# CC2530.net
KiCad netlist of a schematic drawn in Altium Designer
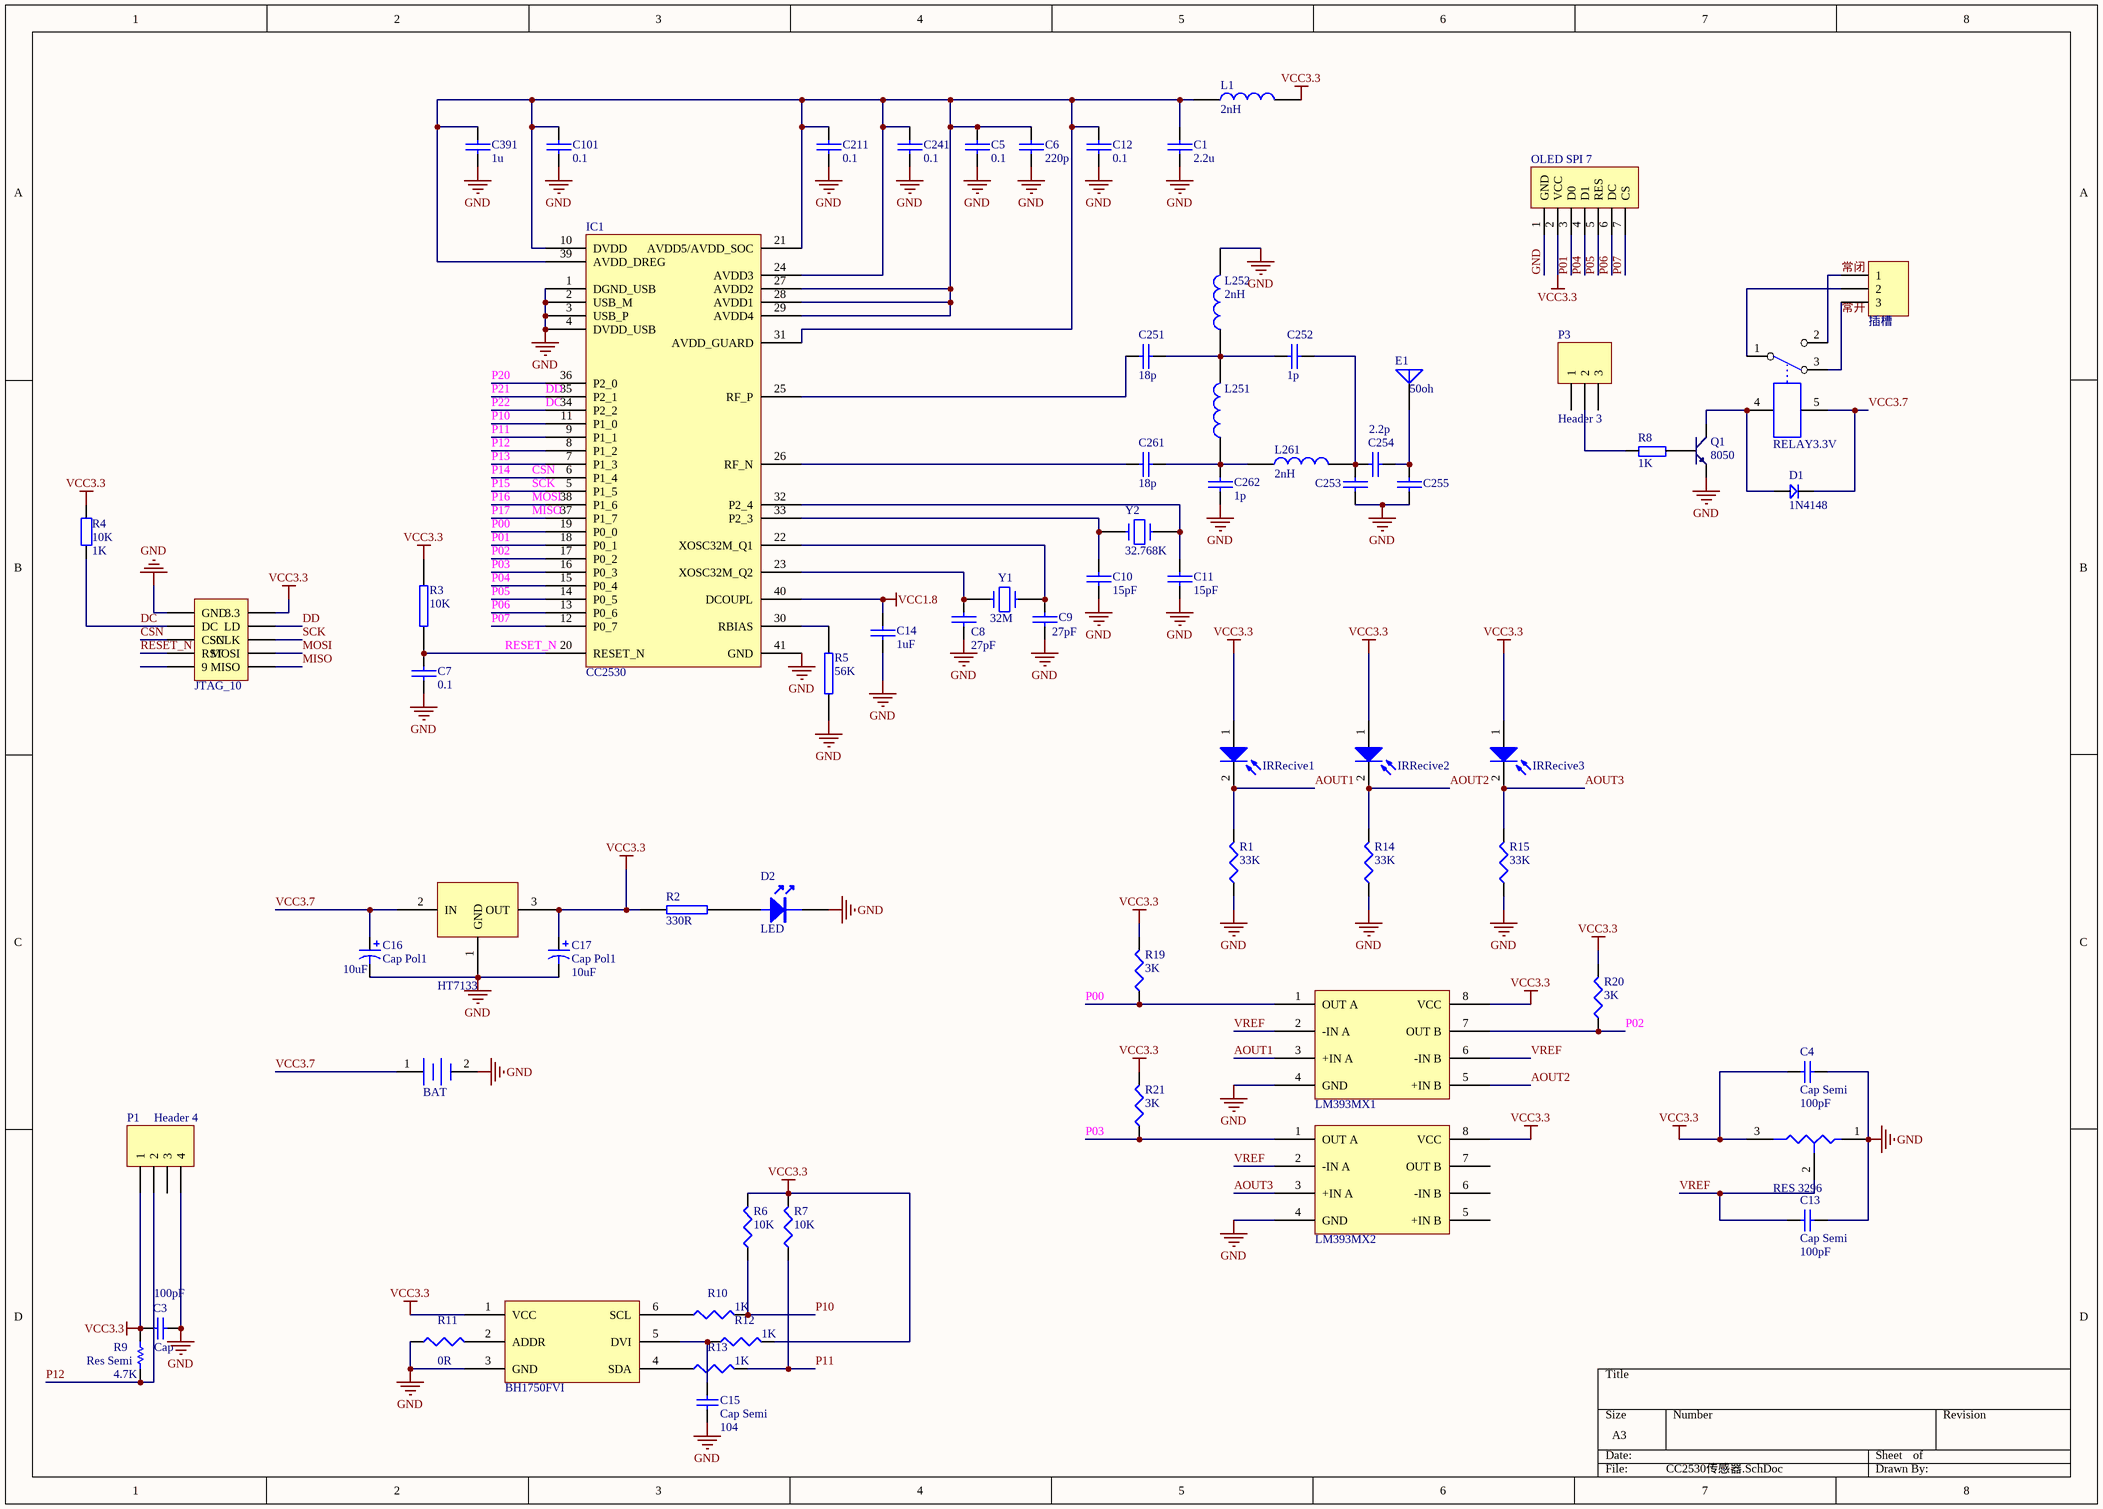
[diagram p0: CC2530传感器.SchDoc]

(export (version "E")
  (design (tool "Eeschema 10.0.6"))
  (components
    (comp (ref "BAT") (value "BAT") (footprint "BAT") (libsource (lib "my Integrated lib ") (part "BAT")))
    (comp (ref "BH1750FVI")
      (value "BH1750FVI")
      (footprint "BH1750FVI")
      (libsource (lib "my Integrated lib ") (part "BH1750FVI"))
    )
    (comp (ref "C1")
      (value "2.2u")
      (footprint "J1-0603")
      (description "Capacitor")
      (libsource (lib "Miscellaneous Devices") (part "CAP"))
    )
    (comp (ref "C3")
      (value "Cap")
      (footprint "J1-0603")
      (description "Capacitor")
      (fields (field (name "ALTIUM_VALUE") "100pF") (field (name "PUBLISHER") "Altium Limited"))
      (libsource (lib "Miscellaneous Devices") (part "Cap"))
    )
    (comp (ref "C4")
      (value "Cap Semi")
      (footprint "3.5X2.8X1.9")
      (description "Capacitor (Semiconductor SIM Model)")
      (fields (field (name "ALTIUM_VALUE") "100pF") (field (name "PUBLISHER") "Altium Limited"))
      (libsource (lib "Miscellaneous Devices") (part "Cap Semi"))
    )
    (comp (ref "C5")
      (value "0.1")
      (footprint "J1-0603")
      (description "Capacitor")
      (libsource (lib "Miscellaneous Devices") (part "CAP"))
    )
    (comp (ref "C6")
      (value "220p")
      (footprint "J1-0603")
      (description "Capacitor")
      (libsource (lib "Miscellaneous Devices") (part "CAP"))
    )
    (comp (ref "C7")
      (value "0.1")
      (footprint "J1-0603")
      (description "Capacitor")
      (libsource (lib "Miscellaneous Devices") (part "CAP"))
    )
    (comp (ref "C8")
      (value "27pF")
      (footprint "J1-0603")
      (description "Capacitor")
      (libsource (lib "Miscellaneous Devices") (part "CAP"))
    )
    (comp (ref "C9")
      (value "27pF")
      (footprint "J1-0603")
      (description "Capacitor")
      (libsource (lib "Miscellaneous Devices") (part "CAP"))
    )
    (comp (ref "C10")
      (value "15pF")
      (footprint "J1-0603")
      (description "Capacitor")
      (libsource (lib "Miscellaneous Devices") (part "CAP"))
    )
    (comp (ref "C11")
      (value "15pF")
      (footprint "J1-0603")
      (description "Capacitor")
      (libsource (lib "Miscellaneous Devices") (part "CAP"))
    )
    (comp (ref "C12")
      (value "0.1")
      (footprint "J1-0603")
      (description "Capacitor")
      (libsource (lib "Miscellaneous Devices") (part "CAP"))
    )
    (comp (ref "C13")
      (value "Cap Semi")
      (footprint "3.5X2.8X1.9")
      (description "Capacitor (Semiconductor SIM Model)")
      (fields (field (name "ALTIUM_VALUE") "100pF") (field (name "PUBLISHER") "Altium Limited"))
      (libsource (lib "Miscellaneous Devices") (part "Cap Semi"))
    )
    (comp (ref "C14")
      (value "1uF")
      (footprint "J1-0603")
      (description "Capacitor")
      (libsource (lib "Miscellaneous Devices") (part "CAP"))
    )
    (comp (ref "C15")
      (value "Cap Semi")
      (footprint "3.5X2.8X1.9")
      (description "Capacitor (Semiconductor SIM Model)")
      (fields (field (name "ALTIUM_VALUE") "104") (field (name "PUBLISHER") "Altium Limited"))
      (libsource (lib "Miscellaneous Devices") (part "Cap Semi"))
    )
    (comp (ref "C16")
      (value "Cap Pol1")
      (footprint "3.5X2.8X1.9")
      (description "Polarized Capacitor (Radial)")
      (fields (field (name "ALTIUM_VALUE") "10uF") (field (name "PUBLISHER") "Altium Limited"))
      (libsource (lib "Miscellaneous Devices") (part "Cap Pol1"))
    )
    (comp (ref "C17")
      (value "Cap Pol1")
      (footprint "3.5X2.8X1.9")
      (description "Polarized Capacitor (Radial)")
      (fields (field (name "ALTIUM_VALUE") "10uF") (field (name "PUBLISHER") "Altium Limited"))
      (libsource (lib "Miscellaneous Devices") (part "Cap Pol1"))
    )
    (comp (ref "C101")
      (value "0.1")
      (footprint "J1-0603")
      (description "Capacitor")
      (libsource (lib "Miscellaneous Devices") (part "CAP"))
    )
    (comp (ref "C211")
      (value "0.1")
      (footprint "J1-0603")
      (description "Capacitor")
      (libsource (lib "Miscellaneous Devices") (part "CAP"))
    )
    (comp (ref "C241")
      (value "0.1")
      (footprint "J1-0603")
      (description "Capacitor")
      (libsource (lib "Miscellaneous Devices") (part "CAP"))
    )
    (comp (ref "C251")
      (value "18p")
      (footprint "J1-0603")
      (description "Capacitor")
      (libsource (lib "Miscellaneous Devices") (part "CAP"))
    )
    (comp (ref "C252")
      (value "1p")
      (footprint "J1-0603")
      (description "Capacitor")
      (libsource (lib "Miscellaneous Devices") (part "CAP"))
    )
    (comp (ref "C253")
      (value "~")
      (footprint "J1-0603")
      (description "Capacitor")
      (libsource (lib "Miscellaneous Devices") (part "CAP"))
    )
    (comp (ref "C254")
      (value "2.2p")
      (footprint "J1-0603")
      (description "Capacitor")
      (libsource (lib "Miscellaneous Devices") (part "CAP"))
    )
    (comp (ref "C255")
      (value "~")
      (footprint "J1-0603")
      (description "Capacitor")
      (libsource (lib "Miscellaneous Devices") (part "CAP"))
    )
    (comp (ref "C261")
      (value "18p")
      (footprint "J1-0603")
      (description "Capacitor")
      (libsource (lib "Miscellaneous Devices") (part "CAP"))
    )
    (comp (ref "C262")
      (value "1p")
      (footprint "J1-0603")
      (description "Capacitor")
      (libsource (lib "Miscellaneous Devices") (part "CAP"))
    )
    (comp (ref "C391")
      (value "1u")
      (footprint "J1-0603")
      (description "Capacitor")
      (libsource (lib "Miscellaneous Devices") (part "CAP"))
    )
    (comp (ref "D1") (value "1N4148") (footprint "C1206") (libsource (lib "my Integrated lib ") (part "D")))
    (comp (ref "D2")
      (value "LED")
      (footprint "3.2X1.6X1.1")
      (libsource (lib "Miscellaneous Devices") (part "LED"))
    )
    (comp (ref "E1")
      (value "50oh")
      (footprint "ANT")
      (description "Generic Antenna")
      (libsource (lib "Miscellaneous Devices") (part "ANTENNA"))
    )
    (comp (ref "HT7133")
      (value "HT7133")
      (footprint "HT7133")
      (libsource (lib "my Integrated lib ") (part "HT7133"))
    )
    (comp (ref "IC1") (value "CC2530") (footprint "QFN40_RHA") (libsource (lib "集成") (part "CC2530")))
    (comp (ref "IRRecive1")
      (value "IRRecive")
      (footprint "IRRecive")
      (libsource (lib "my Integrated lib ") (part "IRRecive"))
    )
    (comp (ref "IRRecive2")
      (value "IRRecive")
      (footprint "IRRecive")
      (libsource (lib "my Integrated lib ") (part "IRRecive"))
    )
    (comp (ref "IRRecive3")
      (value "IRRecive")
      (footprint "IRRecive")
      (libsource (lib "my Integrated lib ") (part "IRRecive"))
    )
    (comp (ref "JTAG_10")
      (value "JTAG_10")
      (footprint "JTAG_10")
      (libsource (lib "my Integrated lib ") (part "JTAG_10"))
    )
    (comp (ref "L1")
      (value "2nH")
      (footprint "J1-0603")
      (libsource (lib "Miscellaneous Devices") (part "INDUCTOR"))
    )
    (comp (ref "L251")
      (value "~")
      (footprint "J1-0603")
      (libsource (lib "Miscellaneous Devices") (part "INDUCTOR"))
    )
    (comp (ref "L252")
      (value "2nH")
      (footprint "J1-0603")
      (libsource (lib "Miscellaneous Devices") (part "INDUCTOR"))
    )
    (comp (ref "L261")
      (value "2nH")
      (footprint "J1-0603")
      (libsource (lib "Miscellaneous Devices") (part "INDUCTOR"))
    )
    (comp (ref "LM393MX1")
      (value "LM393MX")
      (footprint "LM393MX")
      (libsource (lib "my Integrated lib ") (part "LM393MX"))
    )
    (comp (ref "LM393MX2")
      (value "LM393MX")
      (footprint "LM393MX")
      (libsource (lib "my Integrated lib ") (part "LM393MX"))
    )
    (comp (ref "OLED SPI 7")
      (value "OLED SPI 7")
      (footprint "OLED SPI 7")
      (libsource (lib "my Integrated lib ") (part "OLED SPI 7"))
    )
    (comp (ref "P1")
      (value "Header 4")
      (footprint "HDR1X4")
      (description "Header, 4-Pin")
      (fields (field (name "PUBLISHER") "Altium Limited"))
      (libsource (lib "Miscellaneous Connectors") (part "Header 4"))
    )
    (comp (ref "P3")
      (value "Header 3")
      (footprint "HDR1X3")
      (description "Header, 3-Pin")
      (fields (field (name "PUBLISHER") "Altium Limited"))
      (libsource (lib "Miscellaneous Connectors") (part "Header 3"))
    )
    (comp (ref "Q1")
      (value "8050")
      (footprint "SOT-23R")
      (description "8050/BCW846/BCW847")
      (libsource (lib "my Integrated lib ") (part "NPN"))
    )
    (comp (ref "R1")
      (value "33K")
      (footprint "J1-0603")
      (description "Resistor")
      (fields (field (name "Comment") "Res3") (field (name "PUBLISHER") "Altium Limited"))
      (libsource (lib "Miscellaneous Devices") (part "Res3"))
    )
    (comp (ref "R2")
      (value "330R")
      (footprint "J1-0603")
      (libsource (lib "Miscellaneous Devices") (part "RES2"))
    )
    (comp (ref "R3")
      (value "10K")
      (footprint "J1-0603")
      (libsource (lib "Miscellaneous Devices") (part "RES2"))
    )
    (comp (ref "R4")
      (value "10K")
      (footprint "J1-0603")
      (fields (field (name "ALTIUM_VALUE") "1K"))
      (libsource (lib "集成库") (part "res0402"))
    )
    (comp (ref "R5")
      (value "56K")
      (footprint "J1-0603")
      (libsource (lib "Miscellaneous Devices") (part "RES2"))
    )
    (comp (ref "R6")
      (value "10K")
      (footprint "J1-0603")
      (description "Resistor")
      (fields (field (name "Comment") "Res3") (field (name "PUBLISHER") "Altium Limited"))
      (libsource (lib "Miscellaneous Devices") (part "Res3"))
    )
    (comp (ref "R7")
      (value "10K")
      (footprint "J1-0603")
      (description "Resistor")
      (fields (field (name "Comment") "Res3") (field (name "PUBLISHER") "Altium Limited"))
      (libsource (lib "Miscellaneous Devices") (part "Res3"))
    )
    (comp (ref "R8") (value "1K") (footprint "J1-0603") (libsource (lib "my Integrated lib ") (part "R")))
    (comp (ref "R9")
      (value "Res Semi")
      (footprint "J1-0603")
      (description "Semiconductor Resistor")
      (fields (field (name "ALTIUM_VALUE") "4.7K") (field (name "PUBLISHER") "Altium Limited"))
      (libsource (lib "Miscellaneous Devices") (part "Res Semi"))
    )
    (comp (ref "R10")
      (value "1K")
      (footprint "J1-0603")
      (description "Resistor")
      (fields (field (name "Comment") "Res3") (field (name "PUBLISHER") "Altium Limited"))
      (libsource (lib "Miscellaneous Devices") (part "Res3"))
    )
    (comp (ref "R11")
      (value "0R")
      (footprint "J1-0603")
      (description "Resistor")
      (fields (field (name "Comment") "Res3") (field (name "PUBLISHER") "Altium Limited"))
      (libsource (lib "Miscellaneous Devices") (part "Res3"))
    )
    (comp (ref "R12")
      (value "1K")
      (footprint "J1-0603")
      (description "Resistor")
      (fields (field (name "Comment") "Res3") (field (name "PUBLISHER") "Altium Limited"))
      (libsource (lib "Miscellaneous Devices") (part "Res3"))
    )
    (comp (ref "R13")
      (value "1K")
      (footprint "J1-0603")
      (description "Resistor")
      (fields (field (name "Comment") "Res3") (field (name "PUBLISHER") "Altium Limited"))
      (libsource (lib "Miscellaneous Devices") (part "Res3"))
    )
    (comp (ref "R14")
      (value "33K")
      (footprint "J1-0603")
      (description "Resistor")
      (fields (field (name "Comment") "Res3") (field (name "PUBLISHER") "Altium Limited"))
      (libsource (lib "Miscellaneous Devices") (part "Res3"))
    )
    (comp (ref "R15")
      (value "33K")
      (footprint "J1-0603")
      (description "Resistor")
      (fields (field (name "Comment") "Res3") (field (name "PUBLISHER") "Altium Limited"))
      (libsource (lib "Miscellaneous Devices") (part "Res3"))
    )
    (comp (ref "R19")
      (value "3K")
      (footprint "J1-0603")
      (description "Resistor")
      (fields (field (name "Comment") "Res3") (field (name "PUBLISHER") "Altium Limited"))
      (libsource (lib "Miscellaneous Devices") (part "Res3"))
    )
    (comp (ref "R20")
      (value "3K")
      (footprint "J1-0603")
      (description "Resistor")
      (fields (field (name "Comment") "Res3") (field (name "PUBLISHER") "Altium Limited"))
      (libsource (lib "Miscellaneous Devices") (part "Res3"))
    )
    (comp (ref "R21")
      (value "3K")
      (footprint "J1-0603")
      (description "Resistor")
      (fields (field (name "Comment") "Res3") (field (name "PUBLISHER") "Altium Limited"))
      (libsource (lib "Miscellaneous Devices") (part "Res3"))
    )
    (comp (ref "RELAY3.3V")
      (value "RELAY3.3V")
      (footprint "RELAY3.3V")
      (libsource (lib "my Integrated lib ") (part "RELAY3.3V"))
    )
    (comp (ref "RES 3296")
      (value "RES 3296")
      (footprint "RES 3296")
      (libsource (lib "my Integrated lib ") (part "RES 3296"))
    )
    (comp (ref "Y1")
      (value "32M")
      (footprint "XTAL_US")
      (description "Crystal")
      (libsource (lib "Miscellaneous Devices") (part "CRYSTAL"))
    )
    (comp (ref "Y2")
      (value "32.768K")
      (footprint "XTAL 32M")
      (description "Crystal")
      (libsource (lib "Miscellaneous Devices") (part "CRYSTAL"))
    )
    (comp (ref "插槽") (value "插槽") (footprint "杜邦线插槽") (libsource (lib "my Integrated lib ") (part "插槽")))
  )
  (nets
    (net (code "1") (name "/AOUT1") (class "Default")
      (node (ref "IRRecive1") (pin "2") (pinfunction "K_2") (pintype "passive"))
      (node (ref "LM393MX1") (pin "3") (pinfunction "+IN_A_3") (pintype "passive"))
      (node (ref "R1") (pin "2") (pinfunction "2_2") (pintype "passive"))
    )
    (net (code "2") (name "/AOUT2") (class "Default")
      (node (ref "IRRecive2") (pin "2") (pinfunction "K_2") (pintype "passive"))
      (node (ref "LM393MX1") (pin "5") (pinfunction "+IN_B_5") (pintype "passive"))
      (node (ref "R14") (pin "2") (pinfunction "2_2") (pintype "passive"))
    )
    (net (code "3") (name "/AOUT3") (class "Default")
      (node (ref "IRRecive3") (pin "2") (pinfunction "K_2") (pintype "passive"))
      (node (ref "LM393MX2") (pin "3") (pinfunction "+IN_A_3") (pintype "passive"))
      (node (ref "R15") (pin "2") (pinfunction "2_2") (pintype "passive"))
    )
    (net (code "4") (name "/CSN") (class "Default")
      (node (ref "IC1") (pin "6") (pinfunction "P1_4_6") (pintype "passive"))
      (node (ref "JTAG_10") (pin "5") (pinfunction "CSN_5") (pintype "passive"))
    )
    (net (code "5") (name "/DC") (class "Default")
      (node (ref "IC1") (pin "34") (pinfunction "P2_2_34") (pintype "passive"))
      (node (ref "JTAG_10") (pin "3") (pinfunction "DC_3") (pintype "passive"))
      (node (ref "R4") (pin "1") (pinfunction "1_1") (pintype "passive"))
    )
    (net (code "6") (name "/DD") (class "Default")
      (node (ref "IC1") (pin "35") (pinfunction "P2_1_35") (pintype "passive"))
      (node (ref "JTAG_10") (pin "4") (pinfunction "LD_4") (pintype "passive"))
    )
    (net (code "7") (name "/MISO") (class "Default")
      (node (ref "IC1") (pin "37") (pinfunction "P1_7_37") (pintype "passive"))
      (node (ref "JTAG_10") (pin "10") (pinfunction "MISO_10") (pintype "passive"))
    )
    (net (code "8") (name "/MOSI") (class "Default")
      (node (ref "IC1") (pin "38") (pinfunction "P1_6_38") (pintype "passive"))
      (node (ref "JTAG_10") (pin "8") (pinfunction "MOSI_8") (pintype "passive"))
    )
    (net (code "9") (name "/P00") (class "Default")
      (node (ref "IC1") (pin "19") (pinfunction "P0_0_19") (pintype "passive"))
      (node (ref "LM393MX1") (pin "1") (pinfunction "OUT_A_1") (pintype "passive"))
      (node (ref "R19") (pin "1") (pinfunction "1_1") (pintype "passive"))
    )
    (net (code "10") (name "/P01") (class "Default")
      (node (ref "IC1") (pin "18") (pinfunction "P0_1_18") (pintype "passive"))
      (node (ref "OLED SPI 7") (pin "3") (pinfunction "D0_3") (pintype "passive"))
    )
    (net (code "11") (name "/P02") (class "Default")
      (node (ref "IC1") (pin "17") (pinfunction "P0_2_17") (pintype "passive"))
      (node (ref "LM393MX1") (pin "7") (pinfunction "OUT_B_7") (pintype "passive"))
      (node (ref "R20") (pin "1") (pinfunction "1_1") (pintype "passive"))
    )
    (net (code "12") (name "/P03") (class "Default")
      (node (ref "IC1") (pin "16") (pinfunction "P0_3_16") (pintype "passive"))
      (node (ref "LM393MX2") (pin "1") (pinfunction "OUT_A_1") (pintype "passive"))
      (node (ref "R21") (pin "1") (pinfunction "1_1") (pintype "passive"))
    )
    (net (code "13") (name "/P04") (class "Default")
      (node (ref "IC1") (pin "15") (pinfunction "P0_4_15") (pintype "passive"))
      (node (ref "OLED SPI 7") (pin "4") (pinfunction "D1_4") (pintype "passive"))
    )
    (net (code "14") (name "/P05") (class "Default")
      (node (ref "IC1") (pin "14") (pinfunction "P0_5_14") (pintype "passive"))
      (node (ref "OLED SPI 7") (pin "5") (pinfunction "RES_5") (pintype "passive"))
    )
    (net (code "15") (name "/P06") (class "Default")
      (node (ref "IC1") (pin "13") (pinfunction "P0_6_13") (pintype "passive"))
      (node (ref "OLED SPI 7") (pin "6") (pinfunction "DC_6") (pintype "passive"))
    )
    (net (code "16") (name "/P07") (class "Default")
      (node (ref "IC1") (pin "12") (pinfunction "P0_7_12") (pintype "passive"))
      (node (ref "OLED SPI 7") (pin "7") (pinfunction "CS_7") (pintype "passive"))
    )
    (net (code "17") (name "/P10") (class "Default")
      (node (ref "IC1") (pin "11") (pinfunction "P1_0_11") (pintype "passive"))
      (node (ref "R10") (pin "2") (pinfunction "2_2") (pintype "passive"))
      (node (ref "R6") (pin "1") (pinfunction "1_1") (pintype "passive"))
    )
    (net (code "18") (name "/P11") (class "Default")
      (node (ref "IC1") (pin "9") (pinfunction "P1_1_9") (pintype "passive"))
      (node (ref "R13") (pin "2") (pinfunction "2_2") (pintype "passive"))
      (node (ref "R7") (pin "1") (pinfunction "1_1") (pintype "passive"))
    )
    (net (code "19") (name "/P12") (class "Default")
      (node (ref "IC1") (pin "8") (pinfunction "P1_2_8") (pintype "passive"))
      (node (ref "P1") (pin "2") (pinfunction "2_2") (pintype "passive"))
      (node (ref "R9") (pin "1") (pinfunction "1_1") (pintype "passive"))
    )
    (net (code "20") (name "/P13") (class "Default")
      (node (ref "IC1") (pin "7") (pinfunction "P1_3_7") (pintype "passive"))
    )
    (net (code "21") (name "/P15") (class "Default")
      (node (ref "IC1") (pin "5") (pinfunction "P1_5_5") (pintype "passive"))
      (node (ref "JTAG_10") (pin "6") (pinfunction "SCLK_6") (pintype "passive"))
    )
    (net (code "22") (name "/P20") (class "Default")
      (node (ref "IC1") (pin "36") (pinfunction "P2_0_36") (pintype "passive"))
    )
    (net (code "23") (name "/RESET_N") (class "Default")
      (node (ref "C7") (pin "1") (pinfunction "1_1") (pintype "passive"))
      (node (ref "IC1") (pin "20") (pinfunction "RESET_N_20") (pintype "passive"))
      (node (ref "JTAG_10") (pin "7") (pinfunction "RST_7") (pintype "passive"))
      (node (ref "R3") (pin "1") (pinfunction "1_1") (pintype "passive"))
    )
    (net (code "24") (name "/VCC3.7") (class "Default")
      (node (ref "BAT") (pin "1") (pinfunction "+_1") (pintype "passive"))
      (node (ref "C16") (pin "1") (pinfunction "1_1") (pintype "passive"))
      (node (ref "D1") (pin "2") (pintype "passive"))
      (node (ref "HT7133") (pin "2") (pinfunction "IN_2") (pintype "passive"))
      (node (ref "RELAY3.3V") (pin "5") (pinfunction "5_5") (pintype "passive"))
    )
    (net (code "25") (name "/VREF") (class "Default")
      (node (ref "C13") (pin "1") (pinfunction "1_1") (pintype "passive"))
      (node (ref "LM393MX1") (pin "2") (pinfunction "-IN_A_2") (pintype "passive"))
      (node (ref "LM393MX1") (pin "6") (pinfunction "-IN_B_6") (pintype "passive"))
      (node (ref "LM393MX2") (pin "2") (pinfunction "-IN_A_2") (pintype "passive"))
      (node (ref "RES 3296") (pin "2") (pinfunction "TAP_2") (pintype "passive"))
    )
    (net (code "26") (name "/常开") (class "Default")
      (node (ref "RELAY3.3V") (pin "3") (pinfunction "3_3") (pintype "passive"))
      (node (ref "插槽") (pin "3") (pinfunction "3_3") (pintype "passive"))
    )
    (net (code "27") (name "/常闭") (class "Default")
      (node (ref "RELAY3.3V") (pin "2") (pinfunction "2_2") (pintype "passive"))
      (node (ref "插槽") (pin "1") (pinfunction "1_1") (pintype "passive"))
    )
    (net (code "28") (name "GND") (class "Default")
      (node (ref "BAT") (pin "2") (pinfunction "-_2") (pintype "passive"))
      (node (ref "BH1750FVI") (pin "3") (pinfunction "GND_3") (pintype "passive"))
      (node (ref "C1") (pin "2") (pinfunction "2_2") (pintype "passive"))
      (node (ref "C10") (pin "2") (pinfunction "2_2") (pintype "passive"))
      (node (ref "C101") (pin "2") (pinfunction "2_2") (pintype "passive"))
      (node (ref "C11") (pin "2") (pinfunction "2_2") (pintype "passive"))
      (node (ref "C12") (pin "2") (pinfunction "2_2") (pintype "passive"))
      (node (ref "C13") (pin "2") (pinfunction "2_2") (pintype "passive"))
      (node (ref "C14") (pin "2") (pinfunction "2_2") (pintype "passive"))
      (node (ref "C15") (pin "1") (pinfunction "1_1") (pintype "passive"))
      (node (ref "C16") (pin "2") (pinfunction "2_2") (pintype "passive"))
      (node (ref "C17") (pin "2") (pinfunction "2_2") (pintype "passive"))
      (node (ref "C211") (pin "2") (pinfunction "2_2") (pintype "passive"))
      (node (ref "C241") (pin "2") (pinfunction "2_2") (pintype "passive"))
      (node (ref "C253") (pin "2") (pinfunction "2_2") (pintype "passive"))
      (node (ref "C255") (pin "1") (pinfunction "1_1") (pintype "passive"))
      (node (ref "C262") (pin "2") (pinfunction "2_2") (pintype "passive"))
      (node (ref "C3") (pin "2") (pinfunction "2_2") (pintype "passive"))
      (node (ref "C391") (pin "2") (pinfunction "2_2") (pintype "passive"))
      (node (ref "C4") (pin "2") (pinfunction "2_2") (pintype "passive"))
      (node (ref "C5") (pin "2") (pinfunction "2_2") (pintype "passive"))
      (node (ref "C6") (pin "2") (pinfunction "2_2") (pintype "passive"))
      (node (ref "C7") (pin "2") (pinfunction "2_2") (pintype "passive"))
      (node (ref "C8") (pin "2") (pinfunction "2_2") (pintype "passive"))
      (node (ref "C9") (pin "2") (pinfunction "2_2") (pintype "passive"))
      (node (ref "D2") (pin "K") (pinfunction "2_K") (pintype "passive"))
      (node (ref "HT7133") (pin "1") (pinfunction "GND_1") (pintype "passive"))
      (node (ref "IC1") (pin "1") (pinfunction "DGND_USB_1") (pintype "passive"))
      (node (ref "IC1") (pin "2") (pinfunction "USB_M_2") (pintype "passive"))
      (node (ref "IC1") (pin "3") (pinfunction "USB_P_3") (pintype "passive"))
      (node (ref "IC1") (pin "4") (pinfunction "DVDD_USB_4") (pintype "passive"))
      (node (ref "IC1") (pin "41") (pinfunction "GND_41") (pintype "passive"))
      (node (ref "JTAG_10") (pin "1") (pinfunction "GND_1") (pintype "passive"))
      (node (ref "L252") (pin "2") (pinfunction "2_2") (pintype "passive"))
      (node (ref "LM393MX1") (pin "4") (pinfunction "GND_4") (pintype "passive"))
      (node (ref "LM393MX2") (pin "4") (pinfunction "GND_4") (pintype "passive"))
      (node (ref "OLED SPI 7") (pin "1") (pinfunction "GND_1") (pintype "passive"))
      (node (ref "P1") (pin "4") (pinfunction "4_4") (pintype "passive"))
      (node (ref "Q1") (pin "1") (pinfunction "E_1") (pintype "passive"))
      (node (ref "R1") (pin "1") (pinfunction "1_1") (pintype "passive"))
      (node (ref "R11") (pin "1") (pinfunction "1_1") (pintype "passive"))
      (node (ref "R14") (pin "1") (pinfunction "1_1") (pintype "passive"))
      (node (ref "R15") (pin "1") (pinfunction "1_1") (pintype "passive"))
      (node (ref "R5") (pin "2") (pinfunction "2_2") (pintype "passive"))
      (node (ref "RES 3296") (pin "1") (pinfunction "A_1") (pintype "passive"))
    )
    (net (code "29") (name "Net-(BH1750FVI-ADDR)") (class "Default")
      (node (ref "BH1750FVI") (pin "2") (pinfunction "ADDR_2") (pintype "passive"))
      (node (ref "R11") (pin "2") (pinfunction "2_2") (pintype "passive"))
    )
    (net (code "30") (name "Net-(BH1750FVI-DVI)") (class "Default")
      (node (ref "BH1750FVI") (pin "5") (pinfunction "DVI_5") (pintype "passive"))
      (node (ref "C15") (pin "2") (pinfunction "2_2") (pintype "passive"))
      (node (ref "R12") (pin "1") (pinfunction "1_1") (pintype "passive"))
    )
    (net (code "31") (name "Net-(BH1750FVI-SCL)") (class "Default")
      (node (ref "BH1750FVI") (pin "6") (pinfunction "SCL_6") (pintype "passive"))
      (node (ref "R10") (pin "1") (pinfunction "1_1") (pintype "passive"))
    )
    (net (code "32") (name "Net-(BH1750FVI-SDA)") (class "Default")
      (node (ref "BH1750FVI") (pin "4") (pinfunction "SDA_4") (pintype "passive"))
      (node (ref "R13") (pin "1") (pinfunction "1_1") (pintype "passive"))
    )
    (net (code "33") (name "Net-(C251-Pad2)") (class "Default")
      (node (ref "C251") (pin "2") (pinfunction "2_2") (pintype "passive"))
      (node (ref "C252") (pin "1") (pinfunction "1_1") (pintype "passive"))
      (node (ref "L251") (pin "2") (pinfunction "2_2") (pintype "passive"))
      (node (ref "L252") (pin "1") (pinfunction "1_1") (pintype "passive"))
    )
    (net (code "34") (name "Net-(C252-Pad2)") (class "Default")
      (node (ref "C252") (pin "2") (pinfunction "2_2") (pintype "passive"))
      (node (ref "C253") (pin "1") (pinfunction "1_1") (pintype "passive"))
      (node (ref "C254") (pin "1") (pinfunction "1_1") (pintype "passive"))
      (node (ref "L261") (pin "2") (pinfunction "2_2") (pintype "passive"))
    )
    (net (code "35") (name "Net-(C261-Pad2)") (class "Default")
      (node (ref "C261") (pin "2") (pinfunction "2_2") (pintype "passive"))
      (node (ref "C262") (pin "1") (pinfunction "1_1") (pintype "passive"))
      (node (ref "L251") (pin "1") (pinfunction "1_1") (pintype "passive"))
      (node (ref "L261") (pin "1") (pinfunction "1_1") (pintype "passive"))
    )
    (net (code "36") (name "Net-(D2-1)") (class "Default")
      (node (ref "D2") (pin "A") (pinfunction "1_A") (pintype "passive"))
      (node (ref "R2") (pin "1") (pinfunction "1_1") (pintype "passive"))
    )
    (net (code "37") (name "Net-(E1-A)") (class "Default")
      (node (ref "C254") (pin "2") (pinfunction "2_2") (pintype "passive"))
      (node (ref "C255") (pin "2") (pinfunction "2_2") (pintype "passive"))
      (node (ref "E1") (pin "1") (pinfunction "A_1") (pintype "passive"))
    )
    (net (code "38") (name "Net-(IC1-AVDD1)") (class "Default")
      (node (ref "C1") (pin "1") (pinfunction "1_1") (pintype "passive"))
      (node (ref "C101") (pin "1") (pinfunction "1_1") (pintype "passive"))
      (node (ref "C12") (pin "1") (pinfunction "1_1") (pintype "passive"))
      (node (ref "C211") (pin "1") (pinfunction "1_1") (pintype "passive"))
      (node (ref "C241") (pin "1") (pinfunction "1_1") (pintype "passive"))
      (node (ref "C391") (pin "1") (pinfunction "1_1") (pintype "passive"))
      (node (ref "C5") (pin "1") (pinfunction "1_1") (pintype "passive"))
      (node (ref "C6") (pin "1") (pinfunction "1_1") (pintype "passive"))
      (node (ref "IC1") (pin "10") (pinfunction "DVDD_10") (pintype "passive"))
      (node (ref "IC1") (pin "21") (pinfunction "AVDD5/AVDD_SOC_21") (pintype "passive"))
      (node (ref "IC1") (pin "24") (pinfunction "AVDD3_24") (pintype "passive"))
      (node (ref "IC1") (pin "27") (pinfunction "AVDD2_27") (pintype "passive"))
      (node (ref "IC1") (pin "28") (pinfunction "AVDD1_28") (pintype "passive"))
      (node (ref "IC1") (pin "29") (pinfunction "AVDD4_29") (pintype "passive"))
      (node (ref "IC1") (pin "31") (pinfunction "AVDD_GUARD_31") (pintype "passive"))
      (node (ref "IC1") (pin "39") (pinfunction "AVDD_DREG_39") (pintype "passive"))
      (node (ref "L1") (pin "1") (pinfunction "1_1") (pintype "passive"))
    )
    (net (code "39") (name "Net-(IC1-P2_3)") (class "Default")
      (node (ref "C10") (pin "1") (pinfunction "1_1") (pintype "passive"))
      (node (ref "IC1") (pin "33") (pinfunction "P2_3_33") (pintype "passive"))
      (node (ref "Y2") (pin "2") (pinfunction "2_2") (pintype "passive"))
    )
    (net (code "40") (name "Net-(IC1-P2_4)") (class "Default")
      (node (ref "C11") (pin "1") (pinfunction "1_1") (pintype "passive"))
      (node (ref "IC1") (pin "32") (pinfunction "P2_4_32") (pintype "passive"))
      (node (ref "Y2") (pin "1") (pinfunction "1_1") (pintype "passive"))
    )
    (net (code "41") (name "Net-(IC1-RBIAS)") (class "Default")
      (node (ref "IC1") (pin "30") (pinfunction "RBIAS_30") (pintype "passive"))
      (node (ref "R5") (pin "1") (pinfunction "1_1") (pintype "passive"))
    )
    (net (code "42") (name "Net-(IC1-RF_N)") (class "Default")
      (node (ref "C261") (pin "1") (pinfunction "1_1") (pintype "passive"))
      (node (ref "IC1") (pin "26") (pinfunction "RF_N_26") (pintype "passive"))
    )
    (net (code "43") (name "Net-(IC1-RF_P)") (class "Default")
      (node (ref "C251") (pin "1") (pinfunction "1_1") (pintype "passive"))
      (node (ref "IC1") (pin "25") (pinfunction "RF_P_25") (pintype "passive"))
    )
    (net (code "44") (name "Net-(IC1-XOSC32M_Q1)") (class "Default")
      (node (ref "C9") (pin "1") (pinfunction "1_1") (pintype "passive"))
      (node (ref "IC1") (pin "22") (pinfunction "XOSC32M_Q1_22") (pintype "passive"))
      (node (ref "Y1") (pin "2") (pinfunction "2_2") (pintype "passive"))
    )
    (net (code "45") (name "Net-(IC1-XOSC32M_Q2)") (class "Default")
      (node (ref "C8") (pin "1") (pinfunction "1_1") (pintype "passive"))
      (node (ref "IC1") (pin "23") (pinfunction "XOSC32M_Q2_23") (pintype "passive"))
      (node (ref "Y1") (pin "1") (pinfunction "1_1") (pintype "passive"))
    )
    (net (code "46") (name "Net-(P3-Pad2)") (class "Default")
      (node (ref "P3") (pin "2") (pinfunction "2_2") (pintype "passive"))
      (node (ref "R8") (pin "1") (pintype "passive"))
    )
    (net (code "47") (name "Net-(Q1-B)") (class "Default")
      (node (ref "Q1") (pin "2") (pinfunction "B_2") (pintype "passive"))
      (node (ref "R8") (pin "2") (pintype "passive"))
    )
    (net (code "48") (name "Net-(Q1-C)") (class "Default")
      (node (ref "D1") (pin "1") (pintype "passive"))
      (node (ref "Q1") (pin "3") (pinfunction "C_3") (pintype "passive"))
      (node (ref "RELAY3.3V") (pin "4") (pinfunction "4_4") (pintype "passive"))
    )
    (net (code "49") (name "Net-(RELAY3.3V-Pad1)") (class "Default")
      (node (ref "RELAY3.3V") (pin "1") (pinfunction "1_1") (pintype "passive"))
      (node (ref "插槽") (pin "2") (pinfunction "2_2") (pintype "passive"))
    )
    (net (code "50") (name "VCC1.8") (class "Default")
      (node (ref "C14") (pin "1") (pinfunction "1_1") (pintype "passive"))
      (node (ref "IC1") (pin "40") (pinfunction "DCOUPL_40") (pintype "passive"))
    )
    (net (code "51") (name "VCC3.3") (class "Default")
      (node (ref "BH1750FVI") (pin "1") (pinfunction "VCC_1") (pintype "passive"))
      (node (ref "C17") (pin "1") (pinfunction "1_1") (pintype "passive"))
      (node (ref "C3") (pin "1") (pinfunction "1_1") (pintype "passive"))
      (node (ref "C4") (pin "1") (pinfunction "1_1") (pintype "passive"))
      (node (ref "HT7133") (pin "3") (pinfunction "OUT_3") (pintype "passive"))
      (node (ref "IRRecive1") (pin "1") (pinfunction "A_1") (pintype "passive"))
      (node (ref "IRRecive2") (pin "1") (pinfunction "A_1") (pintype "passive"))
      (node (ref "IRRecive3") (pin "1") (pinfunction "A_1") (pintype "passive"))
      (node (ref "JTAG_10") (pin "2") (pinfunction "3.3_2") (pintype "passive"))
      (node (ref "L1") (pin "2") (pinfunction "2_2") (pintype "passive"))
      (node (ref "LM393MX1") (pin "8") (pinfunction "VCC_8") (pintype "passive"))
      (node (ref "LM393MX2") (pin "8") (pinfunction "VCC_8") (pintype "passive"))
      (node (ref "OLED SPI 7") (pin "2") (pinfunction "VCC_2") (pintype "passive"))
      (node (ref "P1") (pin "1") (pinfunction "1_1") (pintype "passive"))
      (node (ref "R12") (pin "2") (pinfunction "2_2") (pintype "passive"))
      (node (ref "R19") (pin "2") (pinfunction "2_2") (pintype "passive"))
      (node (ref "R2") (pin "2") (pinfunction "2_2") (pintype "passive"))
      (node (ref "R20") (pin "2") (pinfunction "2_2") (pintype "passive"))
      (node (ref "R21") (pin "2") (pinfunction "2_2") (pintype "passive"))
      (node (ref "R3") (pin "2") (pinfunction "2_2") (pintype "passive"))
      (node (ref "R4") (pin "2") (pinfunction "2_2") (pintype "passive"))
      (node (ref "R6") (pin "2") (pinfunction "2_2") (pintype "passive"))
      (node (ref "R7") (pin "2") (pinfunction "2_2") (pintype "passive"))
      (node (ref "R9") (pin "2") (pinfunction "2_2") (pintype "passive"))
      (node (ref "RES 3296") (pin "3") (pinfunction "B_3") (pintype "passive"))
    )
    (net (code "52") (name "unconnected-(JTAG_10-Pad9)") (class "Default")
      (node (ref "JTAG_10") (pin "9") (pinfunction "9_9") (pintype "passive"))
    )
    (net (code "53") (name "unconnected-(LM393MX2-+IN_B-Pad5)") (class "Default")
      (node (ref "LM393MX2") (pin "5") (pinfunction "+IN_B_5") (pintype "passive"))
    )
    (net (code "54") (name "unconnected-(LM393MX2--IN_B-Pad6)") (class "Default")
      (node (ref "LM393MX2") (pin "6") (pinfunction "-IN_B_6") (pintype "passive"))
    )
    (net (code "55") (name "unconnected-(LM393MX2-OUT_B-Pad7)") (class "Default")
      (node (ref "LM393MX2") (pin "7") (pinfunction "OUT_B_7") (pintype "passive"))
    )
    (net (code "56") (name "unconnected-(P1-Pad3)") (class "Default")
      (node (ref "P1") (pin "3") (pinfunction "3_3") (pintype "passive"))
    )
    (net (code "57") (name "unconnected-(P3-Pad1)") (class "Default")
      (node (ref "P3") (pin "1") (pinfunction "1_1") (pintype "passive"))
    )
    (net (code "58") (name "unconnected-(P3-Pad3)") (class "Default")
      (node (ref "P3") (pin "3") (pinfunction "3_3") (pintype "passive"))
    )
  )
)
